# VFD_13ST84GINK.net
KiCad netlist of a schematic drawn in Altium Designer
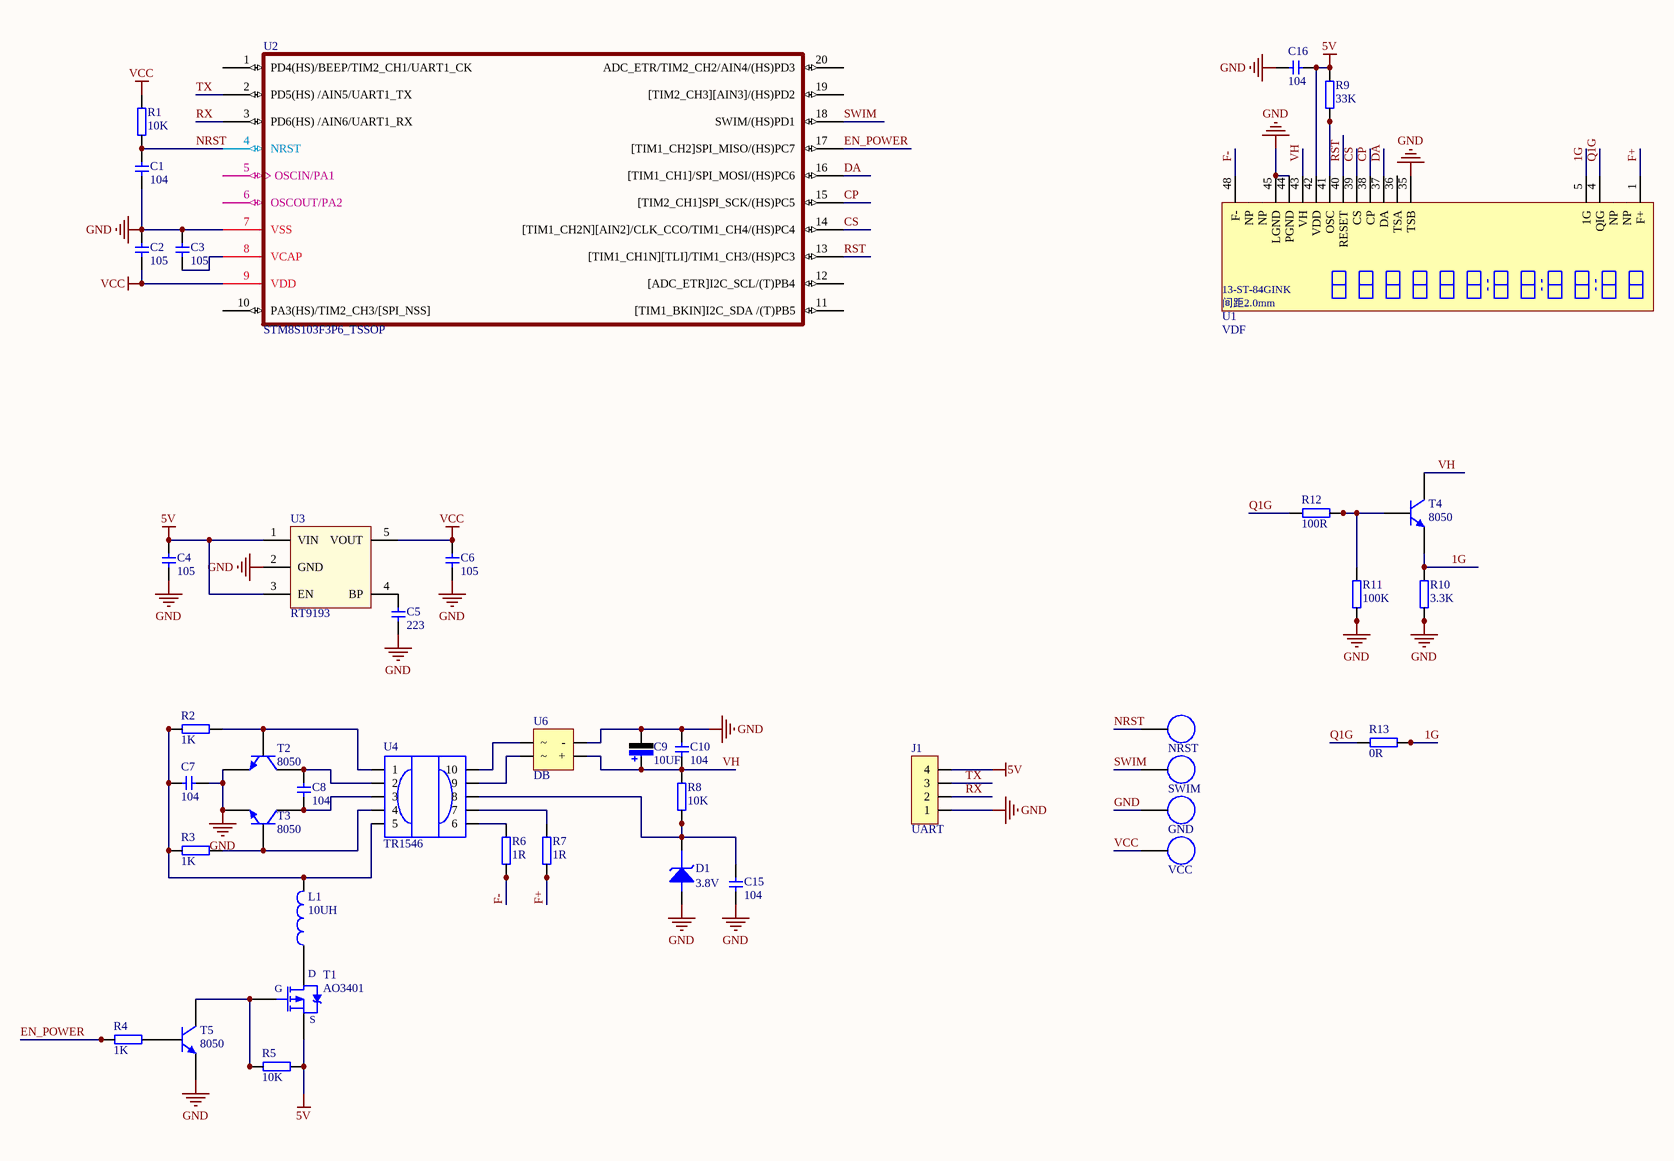
[diagram p0: VFD_13ST84GINK.SchDoc]

(export (version "E")
  (design (tool "Eeschema 10.0.6"))
  (components
    (comp (ref "C1") (value "104") (footprint "C0603") (libsource (lib "my_sch") (part "Cap")))
    (comp (ref "C2") (value "105") (footprint "C0603") (libsource (lib "my_sch") (part "Cap")))
    (comp (ref "C3") (value "105") (footprint "C0603") (libsource (lib "my_sch") (part "Cap")))
    (comp (ref "C4") (value "105") (footprint "C0603") (libsource (lib "my_sch") (part "Cap")))
    (comp (ref "C5") (value "223") (footprint "C0603") (libsource (lib "my_sch") (part "Cap")))
    (comp (ref "C6") (value "105") (footprint "C0603") (libsource (lib "my_sch") (part "Cap")))
    (comp (ref "C7") (value "104") (footprint "C0805") (libsource (lib "my_sch") (part "Cap")))
    (comp (ref "C8") (value "104") (footprint "C0805") (libsource (lib "my_sch") (part "Cap")))
    (comp (ref "C9")
      (value "10UF")
      (footprint "C_SMD_5.0M")
      (description "电解电容")
      (libsource (lib "my_sch") (part "Cap+"))
    )
    (comp (ref "C10") (value "104") (footprint "C0805") (libsource (lib "my_sch") (part "Cap")))
    (comp (ref "C15") (value "104") (footprint "C0603") (libsource (lib "my_sch") (part "Cap")))
    (comp (ref "C16") (value "104") (footprint "C0603") (libsource (lib "my_sch") (part "Cap")))
    (comp (ref "D1")
      (value "3.8V")
      (footprint "LL-34")
      (description "稳压二极管")
      (libsource (lib "my_sch") (part "DZ"))
    )
    (comp (ref "GND")
      (value "GND")
      (footprint "TP_SMT")
      (description "测试点")
      (libsource (lib "my_sch") (part "TP"))
    )
    (comp (ref "J1") (value "UART") (footprint "PIN4") (libsource (lib "my_sch") (part "Pin4")))
    (comp (ref "L1")
      (value "10UH")
      (footprint "L_6045")
      (description "电感")
      (libsource (lib "my_sch") (part "L"))
    )
    (comp (ref "NRST")
      (value "TP")
      (footprint "TP_SMT")
      (description "测试点")
      (libsource (lib "my_sch") (part "TP"))
    )
    (comp (ref "R1") (value "10K") (footprint "R0603") (libsource (lib "my_sch") (part "Res")))
    (comp (ref "R2") (value "1K") (footprint "R0603") (libsource (lib "my_sch") (part "Res")))
    (comp (ref "R3") (value "1K") (footprint "R0603") (libsource (lib "my_sch") (part "Res")))
    (comp (ref "R4") (value "1K") (footprint "R0603") (libsource (lib "my_sch") (part "Res")))
    (comp (ref "R5") (value "10K") (footprint "R0603") (libsource (lib "my_sch") (part "Res")))
    (comp (ref "R6") (value "1R") (footprint "R0805") (libsource (lib "my_sch") (part "Res")))
    (comp (ref "R7") (value "1R") (footprint "R0805") (libsource (lib "my_sch") (part "Res")))
    (comp (ref "R8") (value "10K") (footprint "R0805") (libsource (lib "my_sch") (part "Res")))
    (comp (ref "R9") (value "33K") (footprint "R0603") (libsource (lib "my_sch") (part "Res")))
    (comp (ref "R10") (value "3.3K") (footprint "R0805") (libsource (lib "my_sch") (part "Res")))
    (comp (ref "R11") (value "100K") (footprint "R0603") (libsource (lib "my_sch") (part "Res")))
    (comp (ref "R12") (value "100R") (footprint "R0603") (libsource (lib "my_sch") (part "Res")))
    (comp (ref "R13") (value "0R") (footprint "R0805") (libsource (lib "my_sch") (part "Res")))
    (comp (ref "SWIM")
      (value "TP")
      (footprint "TP_SMT")
      (description "测试点")
      (libsource (lib "my_sch") (part "TP"))
    )
    (comp (ref "T1") (value "AO3401") (footprint "SOT23") (libsource (lib "my_sch") (part "MOS_P")))
    (comp (ref "T2")
      (value "8050")
      (footprint "SOT23")
      (description "NPN三级管")
      (libsource (lib "my_sch") (part "T_NPN_8050"))
    )
    (comp (ref "T3")
      (value "8050")
      (footprint "SOT23")
      (description "NPN三级管")
      (libsource (lib "my_sch") (part "T_NPN_8050_2"))
    )
    (comp (ref "T4")
      (value "8050")
      (footprint "SOT23")
      (description "NPN三级管")
      (libsource (lib "my_sch") (part "T_NPN_8050"))
    )
    (comp (ref "T5")
      (value "8050")
      (footprint "SOT23")
      (description "NPN三级管")
      (libsource (lib "my_sch") (part "T_NPN_8050"))
    )
    (comp (ref "U1")
      (value "VDF")
      (footprint "VDF_13ST84GINK")
      (libsource (lib "my_sch") (part "VFD_13ST84GINK"))
    )
    (comp (ref "U2")
      (value "STM8S103F3P6_TSSOP")
      (footprint "TSSOP20_T_U")
      (description "TSSOP20")
      (libsource (lib "my_sch") (part "STM8S103F3P6_TSSOP"))
    )
    (comp (ref "U3")
      (value "RT9193")
      (footprint "SOT23-5")
      (description "3.3V LDO")
      (libsource (lib "my_sch") (part "RT9193"))
    )
    (comp (ref "U4")
      (value "TR1546")
      (footprint "TR1546")
      (description "VFD变压器")
      (libsource (lib "my_sch") (part "TR1546"))
    )
    (comp (ref "U6")
      (value "DB")
      (footprint "SOIC-4")
      (description "整流桥")
      (libsource (lib "my_sch") (part "DB"))
    )
    (comp (ref "VCC")
      (value "TP")
      (footprint "TP_SMT")
      (description "测试点")
      (libsource (lib "my_sch") (part "TP"))
    )
  )
  (nets
    (net (code "1") (name "/1G") (class "Default")
      (node (ref "R10") (pin "2") (pinfunction "2_2") (pintype "passive"))
      (node (ref "R13") (pin "1") (pinfunction "1_1") (pintype "passive"))
      (node (ref "T4") (pin "2") (pinfunction "E_2") (pintype "passive"))
      (node (ref "U1") (pin "5") (pinfunction "1G_5") (pintype "passive"))
    )
    (net (code "2") (name "/CP") (class "Default")
      (node (ref "U1") (pin "38") (pinfunction "CP_38") (pintype "passive"))
      (node (ref "U2") (pin "15") (pinfunction "[TIM2_CH1]SPI_SCK/(HS)PC5_15") (pintype "bidirectional"))
    )
    (net (code "3") (name "/CS") (class "Default")
      (node (ref "U1") (pin "39") (pinfunction "CS_39") (pintype "passive"))
      (node (ref "U2") (pin "14") (pinfunction "[TIM1_CH2N][AIN2]/CLK_CCO/TIM1_CH4/(HS)PC4_14") (pintype "bidirectional"))
    )
    (net (code "4") (name "/DA") (class "Default")
      (node (ref "U1") (pin "37") (pinfunction "DA_37") (pintype "passive"))
      (node (ref "U2") (pin "16") (pinfunction "[TIM1_CH1]/SPI_MOSI/(HS)PC6_16") (pintype "bidirectional"))
    )
    (net (code "5") (name "/EN_POWER") (class "Default")
      (node (ref "R4") (pin "1") (pinfunction "1_1") (pintype "passive"))
      (node (ref "U2") (pin "17") (pinfunction "[TIM1_CH2]SPI_MISO/(HS)PC7_17") (pintype "bidirectional"))
    )
    (net (code "6") (name "/F+") (class "Default")
      (node (ref "R7") (pin "1") (pinfunction "1_1") (pintype "passive"))
      (node (ref "U1") (pin "1") (pinfunction "F+_1") (pintype "passive"))
    )
    (net (code "7") (name "/F-") (class "Default")
      (node (ref "R6") (pin "1") (pinfunction "1_1") (pintype "passive"))
      (node (ref "U1") (pin "48") (pinfunction "F-_48") (pintype "passive"))
    )
    (net (code "8") (name "/NRST") (class "Default")
      (node (ref "C1") (pin "2") (pinfunction "2_2") (pintype "passive"))
      (node (ref "NRST") (pin "1") (pinfunction "1_1") (pintype "passive"))
      (node (ref "R1") (pin "1") (pinfunction "1_1") (pintype "passive"))
      (node (ref "U2") (pin "4") (pinfunction "NRST_4") (pintype "bidirectional"))
    )
    (net (code "9") (name "/Q1G") (class "Default")
      (node (ref "R12") (pin "2") (pinfunction "2_2") (pintype "passive"))
      (node (ref "R13") (pin "2") (pinfunction "2_2") (pintype "passive"))
      (node (ref "U1") (pin "4") (pinfunction "QIG_4") (pintype "passive"))
    )
    (net (code "10") (name "/RST") (class "Default")
      (node (ref "U1") (pin "40") (pinfunction "RESET_40") (pintype "passive"))
      (node (ref "U2") (pin "13") (pinfunction "[TIM1_CH1N][TLI]/TIM1_CH3/(HS)PC3_13") (pintype "bidirectional"))
    )
    (net (code "11") (name "/RX") (class "Default")
      (node (ref "J1") (pin "2") (pinfunction "2_2") (pintype "passive"))
      (node (ref "U2") (pin "3") (pinfunction "PD6(HS)_/AIN6/UART1_RX_3") (pintype "bidirectional"))
    )
    (net (code "12") (name "/SWIM") (class "Default")
      (node (ref "SWIM") (pin "1") (pinfunction "1_1") (pintype "passive"))
      (node (ref "U2") (pin "18") (pinfunction "SWIM/(HS)PD1_18") (pintype "bidirectional"))
    )
    (net (code "13") (name "/TX") (class "Default")
      (node (ref "J1") (pin "3") (pinfunction "3_3") (pintype "passive"))
      (node (ref "U2") (pin "2") (pinfunction "PD5(HS)_/AIN5/UART1_TX_2") (pintype "bidirectional"))
    )
    (net (code "14") (name "/VH") (class "Default")
      (node (ref "C10") (pin "1") (pinfunction "1_1") (pintype "passive"))
      (node (ref "C9") (pin "1") (pinfunction "1_1") (pintype "passive"))
      (node (ref "R8") (pin "2") (pinfunction "2_2") (pintype "passive"))
      (node (ref "T4") (pin "3") (pinfunction "C_3") (pintype "passive"))
      (node (ref "U1") (pin "43") (pinfunction "VH_43") (pintype "passive"))
      (node (ref "U6") (pin "3") (pinfunction "+_3") (pintype "passive"))
    )
    (net (code "15") (name "5V") (class "Default")
      (node (ref "C16") (pin "1") (pinfunction "1_1") (pintype "passive"))
      (node (ref "C4") (pin "2") (pinfunction "2_2") (pintype "passive"))
      (node (ref "J1") (pin "4") (pinfunction "4_4") (pintype "passive"))
      (node (ref "R5") (pin "2") (pinfunction "2_2") (pintype "passive"))
      (node (ref "R9") (pin "2") (pinfunction "2_2") (pintype "passive"))
      (node (ref "T1") (pin "2") (pinfunction "S_2") (pintype "passive"))
      (node (ref "U1") (pin "42") (pinfunction "VDD_42") (pintype "passive"))
      (node (ref "U3") (pin "1") (pinfunction "VIN_1") (pintype "power_in"))
      (node (ref "U3") (pin "3") (pinfunction "EN_3") (pintype "power_in"))
    )
    (net (code "16") (name "GND") (class "Default")
      (node (ref "C1") (pin "1") (pinfunction "1_1") (pintype "passive"))
      (node (ref "C10") (pin "2") (pinfunction "2_2") (pintype "passive"))
      (node (ref "C15") (pin "1") (pinfunction "1_1") (pintype "passive"))
      (node (ref "C16") (pin "2") (pinfunction "2_2") (pintype "passive"))
      (node (ref "C2") (pin "2") (pinfunction "2_2") (pintype "passive"))
      (node (ref "C3") (pin "2") (pinfunction "2_2") (pintype "passive"))
      (node (ref "C4") (pin "1") (pinfunction "1_1") (pintype "passive"))
      (node (ref "C5") (pin "1") (pinfunction "1_1") (pintype "passive"))
      (node (ref "C6") (pin "1") (pinfunction "1_1") (pintype "passive"))
      (node (ref "C7") (pin "2") (pinfunction "2_2") (pintype "passive"))
      (node (ref "C9") (pin "2") (pinfunction "2_2") (pintype "passive"))
      (node (ref "D1") (pin "1") (pinfunction "1_1") (pintype "passive"))
      (node (ref "GND") (pin "1") (pinfunction "1_1") (pintype "passive"))
      (node (ref "J1") (pin "1") (pinfunction "1_1") (pintype "passive"))
      (node (ref "R10") (pin "1") (pinfunction "1_1") (pintype "passive"))
      (node (ref "R11") (pin "1") (pinfunction "1_1") (pintype "passive"))
      (node (ref "T2") (pin "2") (pinfunction "E_2") (pintype "passive"))
      (node (ref "T3") (pin "2") (pinfunction "E_2") (pintype "passive"))
      (node (ref "T5") (pin "2") (pinfunction "E_2") (pintype "passive"))
      (node (ref "U1") (pin "35") (pinfunction "TSB_35") (pintype "passive"))
      (node (ref "U1") (pin "44") (pinfunction "PGND_44") (pintype "passive"))
      (node (ref "U1") (pin "45") (pinfunction "LGND_45") (pintype "passive"))
      (node (ref "U2") (pin "7") (pinfunction "VSS_7") (pintype "power_in"))
      (node (ref "U3") (pin "2") (pinfunction "GND_2") (pintype "power_in"))
      (node (ref "U6") (pin "4") (pinfunction "-_4") (pintype "passive"))
    )
    (net (code "17") (name "Net-(C7-Pad1)") (class "Default")
      (node (ref "C7") (pin "1") (pinfunction "1_1") (pintype "passive"))
      (node (ref "L1") (pin "2") (pinfunction "2_2") (pintype "passive"))
      (node (ref "R2") (pin "1") (pinfunction "1_1") (pintype "passive"))
      (node (ref "R3") (pin "1") (pinfunction "1_1") (pintype "passive"))
      (node (ref "U4") (pin "5") (pinfunction "5_5") (pintype "passive"))
    )
    (net (code "18") (name "Net-(C15-Pad2)") (class "Default")
      (node (ref "C15") (pin "2") (pinfunction "2_2") (pintype "passive"))
      (node (ref "D1") (pin "2") (pinfunction "2_2") (pintype "passive"))
      (node (ref "R8") (pin "1") (pinfunction "1_1") (pintype "passive"))
      (node (ref "U4") (pin "8") (pinfunction "8_8") (pintype "passive"))
    )
    (net (code "19") (name "Net-(R6-Pad2)") (class "Default")
      (node (ref "R6") (pin "2") (pinfunction "2_2") (pintype "passive"))
      (node (ref "U4") (pin "6") (pinfunction "6_6") (pintype "passive"))
    )
    (net (code "20") (name "Net-(R7-Pad2)") (class "Default")
      (node (ref "R7") (pin "2") (pinfunction "2_2") (pintype "passive"))
      (node (ref "U4") (pin "7") (pinfunction "7_7") (pintype "passive"))
    )
    (net (code "21") (name "Net-(T1-D)") (class "Default")
      (node (ref "L1") (pin "1") (pinfunction "1_1") (pintype "passive"))
      (node (ref "T1") (pin "3") (pinfunction "D_3") (pintype "passive"))
    )
    (net (code "22") (name "Net-(T1-G)") (class "Default")
      (node (ref "R5") (pin "1") (pinfunction "1_1") (pintype "passive"))
      (node (ref "T1") (pin "1") (pinfunction "G_1") (pintype "passive"))
      (node (ref "T5") (pin "3") (pinfunction "C_3") (pintype "passive"))
    )
    (net (code "23") (name "Net-(T2-B)") (class "Default")
      (node (ref "R2") (pin "2") (pinfunction "2_2") (pintype "passive"))
      (node (ref "T2") (pin "1") (pinfunction "B_1") (pintype "passive"))
      (node (ref "U4") (pin "1") (pinfunction "1_1") (pintype "passive"))
    )
    (net (code "24") (name "Net-(T2-C)") (class "Default")
      (node (ref "C8") (pin "2") (pinfunction "2_2") (pintype "passive"))
      (node (ref "T2") (pin "3") (pinfunction "C_3") (pintype "passive"))
      (node (ref "U4") (pin "2") (pinfunction "2_2") (pintype "passive"))
    )
    (net (code "25") (name "Net-(T3-B)") (class "Default")
      (node (ref "R3") (pin "2") (pinfunction "2_2") (pintype "passive"))
      (node (ref "T3") (pin "1") (pinfunction "B_1") (pintype "passive"))
      (node (ref "U4") (pin "4") (pinfunction "4_4") (pintype "passive"))
    )
    (net (code "26") (name "Net-(T3-C)") (class "Default")
      (node (ref "C8") (pin "1") (pinfunction "1_1") (pintype "passive"))
      (node (ref "T3") (pin "3") (pinfunction "C_3") (pintype "passive"))
      (node (ref "U4") (pin "3") (pinfunction "3_3") (pintype "passive"))
    )
    (net (code "27") (name "Net-(T4-B)") (class "Default")
      (node (ref "R11") (pin "2") (pinfunction "2_2") (pintype "passive"))
      (node (ref "R12") (pin "1") (pinfunction "1_1") (pintype "passive"))
      (node (ref "T4") (pin "1") (pinfunction "B_1") (pintype "passive"))
    )
    (net (code "28") (name "Net-(T5-B)") (class "Default")
      (node (ref "R4") (pin "2") (pinfunction "2_2") (pintype "passive"))
      (node (ref "T5") (pin "1") (pinfunction "B_1") (pintype "passive"))
    )
    (net (code "29") (name "Net-(U1-OSC)") (class "Default")
      (node (ref "R9") (pin "1") (pinfunction "1_1") (pintype "passive"))
      (node (ref "U1") (pin "41") (pinfunction "OSC_41") (pintype "passive"))
    )
    (net (code "30") (name "Net-(U2-VCAP)") (class "Default")
      (node (ref "C3") (pin "1") (pinfunction "1_1") (pintype "passive"))
      (node (ref "U2") (pin "8") (pinfunction "VCAP_8") (pintype "power_in"))
    )
    (net (code "31") (name "Net-(U3-BP)") (class "Default")
      (node (ref "C5") (pin "2") (pinfunction "2_2") (pintype "passive"))
      (node (ref "U3") (pin "4") (pinfunction "BP_4") (pintype "passive"))
    )
    (net (code "32") (name "Net-(U4-Pad9)") (class "Default")
      (node (ref "U4") (pin "9") (pinfunction "9_9") (pintype "passive"))
      (node (ref "U6") (pin "2") (pinfunction "~_2") (pintype "passive"))
    )
    (net (code "33") (name "Net-(U4-Pad10)") (class "Default")
      (node (ref "U4") (pin "10") (pinfunction "10_10") (pintype "passive"))
      (node (ref "U6") (pin "1") (pinfunction "~_1") (pintype "passive"))
    )
    (net (code "34") (name "VCC") (class "Default")
      (node (ref "C2") (pin "1") (pinfunction "1_1") (pintype "passive"))
      (node (ref "C6") (pin "2") (pinfunction "2_2") (pintype "passive"))
      (node (ref "R1") (pin "2") (pinfunction "2_2") (pintype "passive"))
      (node (ref "U2") (pin "9") (pinfunction "VDD_9") (pintype "power_in"))
      (node (ref "U3") (pin "5") (pinfunction "VOUT_5") (pintype "power_in"))
      (node (ref "VCC") (pin "1") (pinfunction "1_1") (pintype "passive"))
    )
    (net (code "35") (name "unconnected-(U1-NP-Pad2)") (class "Default")
      (node (ref "U1") (pin "2") (pinfunction "NP_2") (pintype "passive"))
    )
    (net (code "36") (name "unconnected-(U1-NP-Pad3)") (class "Default")
      (node (ref "U1") (pin "3") (pinfunction "NP_3") (pintype "passive"))
    )
    (net (code "37") (name "unconnected-(U1-NP-Pad46)") (class "Default")
      (node (ref "U1") (pin "46") (pinfunction "NP_46") (pintype "passive"))
    )
    (net (code "38") (name "unconnected-(U1-NP-Pad47)") (class "Default")
      (node (ref "U1") (pin "47") (pinfunction "NP_47") (pintype "passive"))
    )
    (net (code "39") (name "unconnected-(U1-TSA-Pad36)") (class "Default")
      (node (ref "U1") (pin "36") (pinfunction "TSA_36") (pintype "passive"))
    )
    (net (code "40") (name "unconnected-(U2-ADC_ETR{slash}TIM2_CH2{slash}AIN4{slash}(HS)PD3-Pad20)") (class "Default")
      (node (ref "U2") (pin "20") (pinfunction "ADC_ETR/TIM2_CH2/AIN4/(HS)PD3_20") (pintype "bidirectional"))
    )
    (net (code "41") (name "unconnected-(U2-OSCIN{slash}PA1-Pad5)") (class "Default")
      (node (ref "U2") (pin "5") (pinfunction "OSCIN/PA1_5") (pintype "bidirectional"))
    )
    (net (code "42") (name "unconnected-(U2-OSCOUT{slash}PA2-Pad6)") (class "Default")
      (node (ref "U2") (pin "6") (pinfunction "OSCOUT/PA2_6") (pintype "bidirectional"))
    )
    (net (code "43") (name "unconnected-(U2-PA3(HS){slash}TIM2_CH3{slash}[SPI_NSS]-Pad10)") (class "Default")
      (node (ref "U2") (pin "10") (pinfunction "PA3(HS)/TIM2_CH3/[SPI_NSS]_10") (pintype "bidirectional"))
    )
    (net (code "44") (name "unconnected-(U2-PD4(HS){slash}BEEP{slash}TIM2_CH1{slash}UART1_CK-Pad1)") (class "Default")
      (node (ref "U2") (pin "1") (pinfunction "PD4(HS)/BEEP/TIM2_CH1/UART1_CK_1") (pintype "bidirectional"))
    )
    (net (code "45") (name "unconnected-(U2-[ADC_ETR]I2C_SCL{slash}(T)PB4-Pad12)") (class "Default")
      (node (ref "U2") (pin "12") (pinfunction "[ADC_ETR]I2C_SCL/(T)PB4_12") (pintype "bidirectional"))
    )
    (net (code "46") (name "unconnected-(U2-[TIM1_BKIN]I2C_SDA_{slash}(T)PB5-Pad11)") (class "Default")
      (node (ref "U2") (pin "11") (pinfunction "[TIM1_BKIN]I2C_SDA_/(T)PB5_11") (pintype "bidirectional"))
    )
    (net (code "47") (name "unconnected-(U2-[TIM2_CH3][AIN3]{slash}(HS)PD2-Pad19)") (class "Default")
      (node (ref "U2") (pin "19") (pinfunction "[TIM2_CH3][AIN3]/(HS)PD2_19") (pintype "bidirectional"))
    )
  )
)
